# main_board.net
KiCad netlist of a schematic drawn in EAGLE
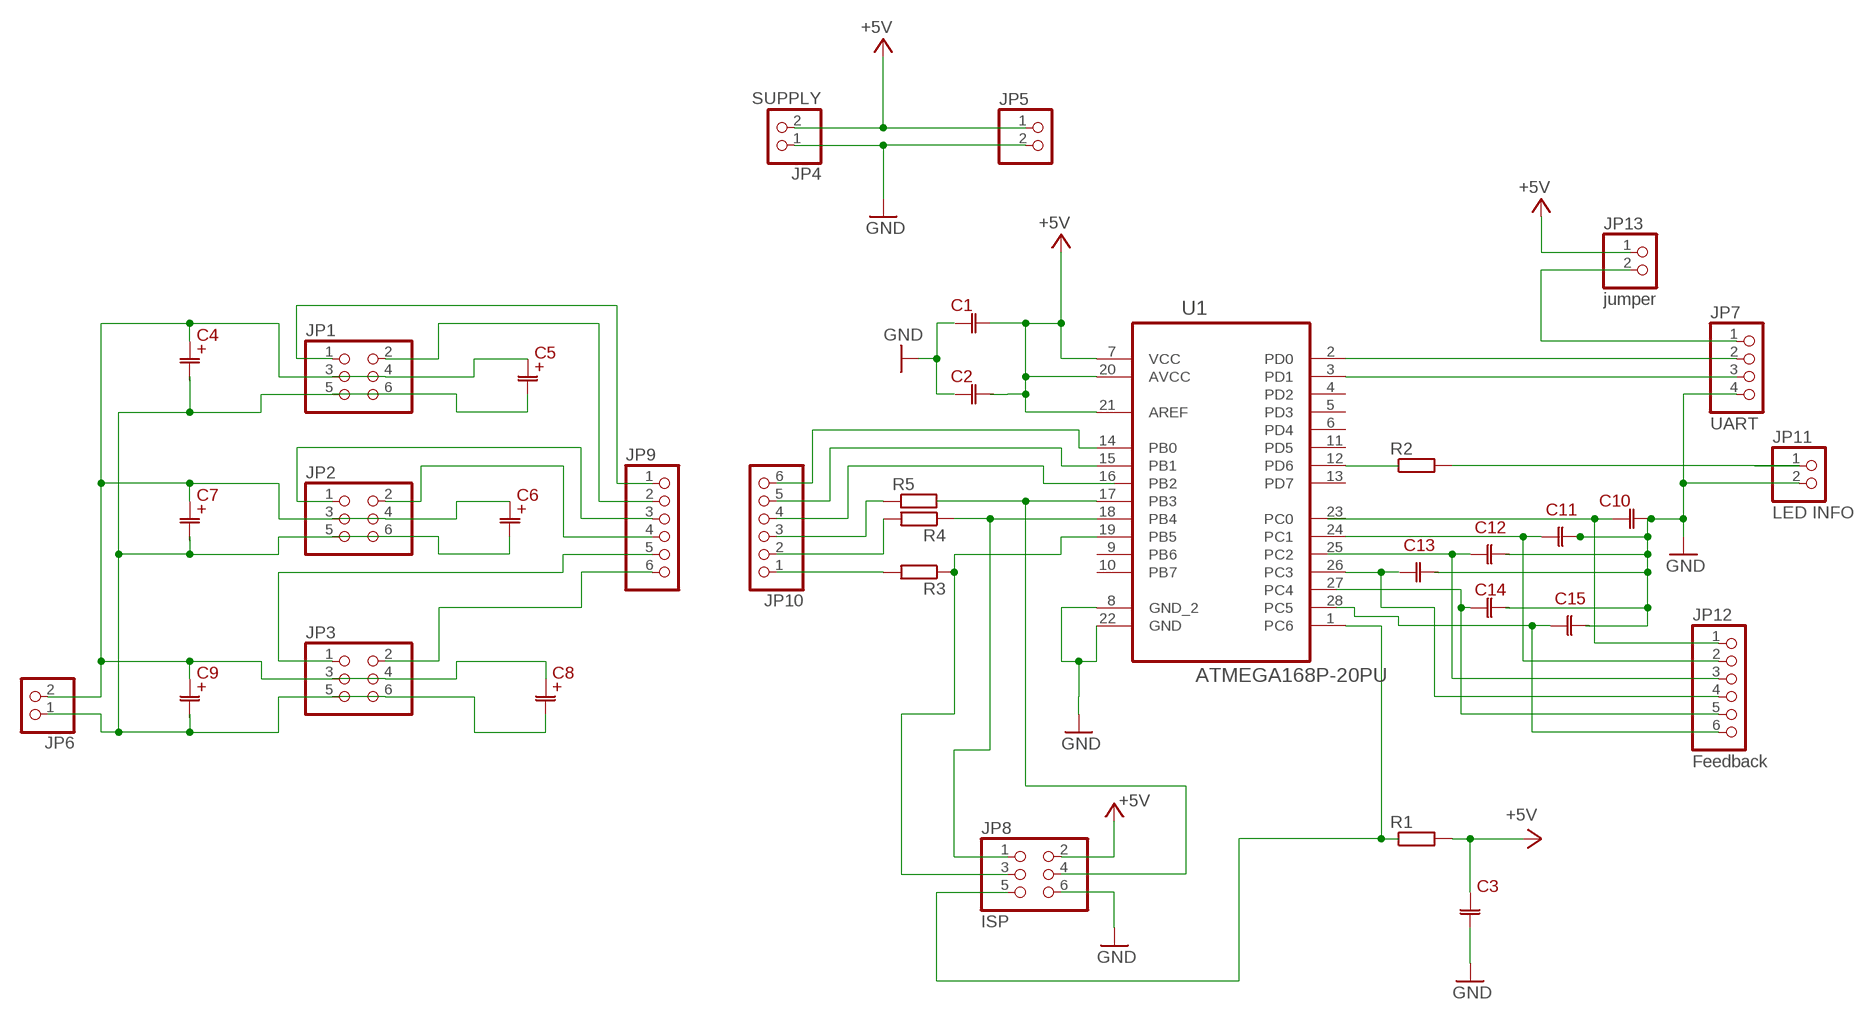
[diagram p0: schematic, sheet 1]

(export (version "E")
  (design (tool "Eeschema 10.0.6"))
  (components
    (comp (ref "C1")
      (value "C-UA")
      (footprint "eagle-import:C2225K")
      (libsource (lib "eagle-import") (part "C-UA"))
    )
    (comp (ref "C2")
      (value "C-UA")
      (footprint "eagle-import:C2225K")
      (libsource (lib "eagle-import") (part "C-UA"))
    )
    (comp (ref "C3")
      (value "C-UA")
      (footprint "eagle-import:C2225K")
      (libsource (lib "eagle-import") (part "C-UA"))
    )
    (comp (ref "C4")
      (value "CPOL-UA")
      (footprint "eagle-import:E3,5-8")
      (libsource (lib "eagle-import") (part "CPOL-UA"))
    )
    (comp (ref "C5")
      (value "CPOL-UA")
      (footprint "eagle-import:E3,5-8")
      (libsource (lib "eagle-import") (part "CPOL-UA"))
    )
    (comp (ref "C6")
      (value "CPOL-UA")
      (footprint "eagle-import:E3,5-8")
      (libsource (lib "eagle-import") (part "CPOL-UA"))
    )
    (comp (ref "C7")
      (value "CPOL-UA")
      (footprint "eagle-import:E3,5-8")
      (libsource (lib "eagle-import") (part "CPOL-UA"))
    )
    (comp (ref "C8")
      (value "CPOL-UA")
      (footprint "eagle-import:E3,5-8")
      (libsource (lib "eagle-import") (part "CPOL-UA"))
    )
    (comp (ref "C9")
      (value "CPOL-UA")
      (footprint "eagle-import:E3,5-8")
      (libsource (lib "eagle-import") (part "CPOL-UA"))
    )
    (comp (ref "C10")
      (value "C-UA")
      (footprint "eagle-import:C2225K")
      (libsource (lib "eagle-import") (part "C-UA"))
    )
    (comp (ref "C11")
      (value "C-UA")
      (footprint "eagle-import:C2225K")
      (libsource (lib "eagle-import") (part "C-UA"))
    )
    (comp (ref "C12")
      (value "C-UA")
      (footprint "eagle-import:C2225K")
      (libsource (lib "eagle-import") (part "C-UA"))
    )
    (comp (ref "C13")
      (value "C-UA")
      (footprint "eagle-import:C2225K")
      (libsource (lib "eagle-import") (part "C-UA"))
    )
    (comp (ref "C14")
      (value "C-UA")
      (footprint "eagle-import:C2225K")
      (libsource (lib "eagle-import") (part "C-UA"))
    )
    (comp (ref "C15")
      (value "C-UA")
      (footprint "eagle-import:C2225K")
      (libsource (lib "eagle-import") (part "C-UA"))
    )
    (comp (ref "JP1")
      (value "PINHD-2X3")
      (footprint "eagle-import:2X03")
      (libsource (lib "eagle-import") (part "PINHD-2X3"))
    )
    (comp (ref "JP2")
      (value "PINHD-2X3")
      (footprint "eagle-import:2X03")
      (libsource (lib "eagle-import") (part "PINHD-2X3"))
    )
    (comp (ref "JP3")
      (value "PINHD-2X3")
      (footprint "eagle-import:2X03")
      (libsource (lib "eagle-import") (part "PINHD-2X3"))
    )
    (comp (ref "JP4")
      (value "SUPPLY")
      (footprint "eagle-import:1X02")
      (libsource (lib "eagle-import") (part "PINHD-1X2"))
    )
    (comp (ref "JP5")
      (value "PINHD-1X2")
      (footprint "eagle-import:1X02")
      (libsource (lib "eagle-import") (part "PINHD-1X2"))
    )
    (comp (ref "JP6")
      (value "PINHD-1X2")
      (footprint "eagle-import:1X02")
      (libsource (lib "eagle-import") (part "PINHD-1X2"))
    )
    (comp (ref "JP7")
      (value "UART")
      (footprint "eagle-import:1X04")
      (libsource (lib "eagle-import") (part "PINHD-1X4"))
    )
    (comp (ref "JP8")
      (value "ISP")
      (footprint "eagle-import:2X03")
      (libsource (lib "eagle-import") (part "PINHD-2X3"))
    )
    (comp (ref "JP9")
      (value "PINHD-1X6")
      (footprint "eagle-import:1X06")
      (libsource (lib "eagle-import") (part "PINHD-1X6"))
    )
    (comp (ref "JP10")
      (value "PINHD-1X6")
      (footprint "eagle-import:1X06")
      (libsource (lib "eagle-import") (part "PINHD-1X6"))
    )
    (comp (ref "JP11")
      (value "LED INFO")
      (footprint "eagle-import:1X02")
      (libsource (lib "eagle-import") (part "PINHD-1X2"))
    )
    (comp (ref "JP12")
      (value "Feedback")
      (footprint "eagle-import:1X06")
      (libsource (lib "eagle-import") (part "PINHD-1X6"))
    )
    (comp (ref "JP13")
      (value "jumper")
      (footprint "eagle-import:1X02")
      (libsource (lib "eagle-import") (part "PINHD-1X2"))
    )
    (comp (ref "R1")
      (value "R-EU_0204/2V")
      (footprint "eagle-import:0204V")
      (libsource (lib "eagle-import") (part "R-EU_0204/2V"))
    )
    (comp (ref "R2")
      (value "R-EU_0204/2V")
      (footprint "eagle-import:0204V")
      (libsource (lib "eagle-import") (part "R-EU_0204/2V"))
    )
    (comp (ref "R3")
      (value "R-EU_0204/2V")
      (footprint "eagle-import:0204V")
      (libsource (lib "eagle-import") (part "R-EU_0204/2V"))
    )
    (comp (ref "R4")
      (value "R-EU_0204/2V")
      (footprint "eagle-import:0204V")
      (libsource (lib "eagle-import") (part "R-EU_0204/2V"))
    )
    (comp (ref "R5")
      (value "R-EU_0204/2V")
      (footprint "eagle-import:0204V")
      (libsource (lib "eagle-import") (part "R-EU_0204/2V"))
    )
    (comp (ref "U1")
      (value "ATMEGA168P-20PU")
      (footprint "eagle-import:DIP254P762X457-28")
      (libsource (lib "eagle-import") (part "ATMEGA168P-20PU"))
    )
  )
  (nets
    (net (code "1") (name "+5V") (class "Default")
      (node (ref "JP13") (pin "1") (pinfunction "1_1") (pintype "passive"))
      (node (ref "JP4") (pin "2") (pinfunction "2_2") (pintype "passive"))
      (node (ref "JP5") (pin "1") (pinfunction "1_1") (pintype "passive"))
      (node (ref "JP8") (pin "2") (pinfunction "2_2") (pintype "passive"))
      (node (ref "R1") (pin "2") (pinfunction "2_2") (pintype "passive"))
      (node (ref "U1") (pin "20") (pinfunction "AVCC_20") (pintype "power_in"))
      (node (ref "U1") (pin "21") (pinfunction "AREF_21") (pintype "input"))
      (node (ref "U1") (pin "7") (pinfunction "VCC_7") (pintype "power_in"))
    )
    (net (code "2") (name "GND") (class "Default")
      (node (ref "C10") (pin "2") (pinfunction "2_2") (pintype "passive"))
      (node (ref "C11") (pin "2") (pinfunction "2_2") (pintype "passive"))
      (node (ref "C12") (pin "2") (pinfunction "2_2") (pintype "passive"))
      (node (ref "C13") (pin "2") (pinfunction "2_2") (pintype "passive"))
      (node (ref "C14") (pin "2") (pinfunction "2_2") (pintype "passive"))
      (node (ref "C15") (pin "2") (pinfunction "2_2") (pintype "passive"))
      (node (ref "C3") (pin "2") (pinfunction "2_2") (pintype "passive"))
      (node (ref "JP11") (pin "2") (pinfunction "2_2") (pintype "passive"))
      (node (ref "JP4") (pin "1") (pinfunction "1_1") (pintype "passive"))
      (node (ref "JP5") (pin "2") (pinfunction "2_2") (pintype "passive"))
      (node (ref "JP7") (pin "4") (pinfunction "4_4") (pintype "passive"))
      (node (ref "JP8") (pin "6") (pinfunction "6_6") (pintype "passive"))
      (node (ref "U1") (pin "22") (pinfunction "GND_22") (pintype "passive"))
      (node (ref "U1") (pin "8") (pinfunction "GND_2_8") (pintype "passive"))
    )
    (net (code "3") (name "Net-(C4-Pad-)") (class "Default")
      (node (ref "C4") (pin "-") (pinfunction "-_-") (pintype "passive"))
      (node (ref "JP1") (pin "5") (pinfunction "5_5") (pintype "passive"))
      (node (ref "JP1") (pin "6") (pinfunction "6_6") (pintype "passive"))
      (node (ref "JP2") (pin "5") (pinfunction "5_5") (pintype "passive"))
      (node (ref "JP2") (pin "6") (pinfunction "6_6") (pintype "passive"))
      (node (ref "JP3") (pin "5") (pinfunction "5_5") (pintype "passive"))
      (node (ref "JP3") (pin "6") (pinfunction "6_6") (pintype "passive"))
      (node (ref "JP6") (pin "1") (pinfunction "1_1") (pintype "passive"))
    )
    (net (code "4") (name "Net-(JP1-Pad1)") (class "Default")
      (node (ref "JP1") (pin "1") (pinfunction "1_1") (pintype "passive"))
      (node (ref "JP9") (pin "1") (pinfunction "1_1") (pintype "passive"))
    )
    (net (code "5") (name "Net-(JP1-Pad2)") (class "Default")
      (node (ref "JP1") (pin "2") (pinfunction "2_2") (pintype "passive"))
      (node (ref "JP9") (pin "2") (pinfunction "2_2") (pintype "passive"))
    )
    (net (code "6") (name "Net-(JP1-Pad3)") (class "Default")
      (node (ref "JP1") (pin "3") (pinfunction "3_3") (pintype "passive"))
      (node (ref "JP1") (pin "4") (pinfunction "4_4") (pintype "passive"))
      (node (ref "JP2") (pin "3") (pinfunction "3_3") (pintype "passive"))
      (node (ref "JP2") (pin "4") (pinfunction "4_4") (pintype "passive"))
      (node (ref "JP3") (pin "3") (pinfunction "3_3") (pintype "passive"))
      (node (ref "JP3") (pin "4") (pinfunction "4_4") (pintype "passive"))
      (node (ref "JP6") (pin "2") (pinfunction "2_2") (pintype "passive"))
    )
    (net (code "7") (name "Net-(JP2-Pad1)") (class "Default")
      (node (ref "JP2") (pin "1") (pinfunction "1_1") (pintype "passive"))
      (node (ref "JP9") (pin "3") (pinfunction "3_3") (pintype "passive"))
    )
    (net (code "8") (name "Net-(JP2-Pad2)") (class "Default")
      (node (ref "JP2") (pin "2") (pinfunction "2_2") (pintype "passive"))
      (node (ref "JP9") (pin "4") (pinfunction "4_4") (pintype "passive"))
    )
    (net (code "9") (name "Net-(JP3-Pad1)") (class "Default")
      (node (ref "JP3") (pin "1") (pinfunction "1_1") (pintype "passive"))
      (node (ref "JP9") (pin "5") (pinfunction "5_5") (pintype "passive"))
    )
    (net (code "10") (name "Net-(JP3-Pad2)") (class "Default")
      (node (ref "JP3") (pin "2") (pinfunction "2_2") (pintype "passive"))
      (node (ref "JP9") (pin "6") (pinfunction "6_6") (pintype "passive"))
    )
    (net (code "11") (name "Net-(JP10-Pad1)") (class "Default")
      (node (ref "JP10") (pin "1") (pinfunction "1_1") (pintype "passive"))
      (node (ref "R3") (pin "2") (pinfunction "2_2") (pintype "passive"))
    )
    (net (code "12") (name "Net-(JP10-Pad2)") (class "Default")
      (node (ref "JP10") (pin "2") (pinfunction "2_2") (pintype "passive"))
      (node (ref "R4") (pin "2") (pinfunction "2_2") (pintype "passive"))
    )
    (net (code "13") (name "Net-(JP10-Pad3)") (class "Default")
      (node (ref "JP10") (pin "3") (pinfunction "3_3") (pintype "passive"))
      (node (ref "R5") (pin "1") (pinfunction "1_1") (pintype "passive"))
    )
    (net (code "14") (name "Net-(JP11-Pad1)") (class "Default")
      (node (ref "JP11") (pin "1") (pinfunction "1_1") (pintype "passive"))
      (node (ref "R2") (pin "2") (pinfunction "2_2") (pintype "passive"))
    )
    (net (code "15") (name "Net-(JP13-Pad2)") (class "Default")
      (node (ref "JP13") (pin "2") (pinfunction "2_2") (pintype "passive"))
      (node (ref "JP7") (pin "1") (pinfunction "1_1") (pintype "passive"))
    )
    (net (code "16") (name "Net-(U1-PB0)") (class "Default")
      (node (ref "JP10") (pin "6") (pinfunction "6_6") (pintype "passive"))
      (node (ref "U1") (pin "14") (pinfunction "PB0_14") (pintype "bidirectional"))
    )
    (net (code "17") (name "Net-(U1-PB1)") (class "Default")
      (node (ref "JP10") (pin "5") (pinfunction "5_5") (pintype "passive"))
      (node (ref "U1") (pin "15") (pinfunction "PB1_15") (pintype "bidirectional"))
    )
    (net (code "18") (name "Net-(U1-PB3)") (class "Default")
      (node (ref "JP8") (pin "4") (pinfunction "4_4") (pintype "passive"))
      (node (ref "U1") (pin "17") (pinfunction "PB3_17") (pintype "bidirectional"))
    )
    (net (code "19") (name "Net-(U1-PB4)") (class "Default")
      (node (ref "JP8") (pin "1") (pinfunction "1_1") (pintype "passive"))
      (node (ref "R4") (pin "1") (pinfunction "1_1") (pintype "passive"))
      (node (ref "U1") (pin "18") (pinfunction "PB4_18") (pintype "bidirectional"))
    )
    (net (code "20") (name "Net-(U1-PB5)") (class "Default")
      (node (ref "JP8") (pin "3") (pinfunction "3_3") (pintype "passive"))
      (node (ref "R3") (pin "1") (pinfunction "1_1") (pintype "passive"))
      (node (ref "U1") (pin "19") (pinfunction "PB5_19") (pintype "bidirectional"))
    )
    (net (code "21") (name "Net-(U1-PC1)") (class "Default")
      (node (ref "JP12") (pin "2") (pinfunction "2_2") (pintype "passive"))
      (node (ref "U1") (pin "24") (pinfunction "PC1_24") (pintype "bidirectional"))
    )
    (net (code "22") (name "Net-(U1-PC3)") (class "Default")
      (node (ref "JP12") (pin "4") (pinfunction "4_4") (pintype "passive"))
      (node (ref "U1") (pin "26") (pinfunction "PC3_26") (pintype "bidirectional"))
    )
    (net (code "23") (name "Net-(U1-PC6)") (class "Default")
      (node (ref "JP8") (pin "5") (pinfunction "5_5") (pintype "passive"))
      (node (ref "R1") (pin "1") (pinfunction "1_1") (pintype "passive"))
      (node (ref "U1") (pin "1") (pinfunction "PC6_1") (pintype "bidirectional"))
    )
    (net (code "24") (name "Net-(U1-PD0)") (class "Default")
      (node (ref "JP7") (pin "2") (pinfunction "2_2") (pintype "passive"))
      (node (ref "U1") (pin "2") (pinfunction "PD0_2") (pintype "bidirectional"))
    )
    (net (code "25") (name "Net-(U1-PD1)") (class "Default")
      (node (ref "JP7") (pin "3") (pinfunction "3_3") (pintype "passive"))
      (node (ref "U1") (pin "3") (pinfunction "PD1_3") (pintype "bidirectional"))
    )
    (net (code "26") (name "Net-(U1-PD6)") (class "Default")
      (node (ref "R2") (pin "1") (pinfunction "1_1") (pintype "passive"))
      (node (ref "U1") (pin "12") (pinfunction "PD6_12") (pintype "bidirectional"))
    )
    (net (code "27") (name "unconnected-(C1-Pad1)") (class "Default")
      (node (ref "C1") (pin "1") (pinfunction "1_1") (pintype "passive"))
    )
    (net (code "28") (name "unconnected-(C1-Pad2)") (class "Default")
      (node (ref "C1") (pin "2") (pinfunction "2_2") (pintype "passive"))
    )
    (net (code "29") (name "unconnected-(C2-Pad1)") (class "Default")
      (node (ref "C2") (pin "1") (pinfunction "1_1") (pintype "passive"))
    )
    (net (code "30") (name "unconnected-(C2-Pad2)") (class "Default")
      (node (ref "C2") (pin "2") (pinfunction "2_2") (pintype "passive"))
    )
    (net (code "31") (name "unconnected-(C3-Pad1)") (class "Default")
      (node (ref "C3") (pin "1") (pinfunction "1_1") (pintype "passive"))
    )
    (net (code "32") (name "unconnected-(C4-Pad+)") (class "Default")
      (node (ref "C4") (pin "+") (pinfunction "+_+") (pintype "passive"))
    )
    (net (code "33") (name "unconnected-(C5-Pad+)") (class "Default")
      (node (ref "C5") (pin "+") (pinfunction "+_+") (pintype "passive"))
    )
    (net (code "34") (name "unconnected-(C5-Pad-)") (class "Default")
      (node (ref "C5") (pin "-") (pinfunction "-_-") (pintype "passive"))
    )
    (net (code "35") (name "unconnected-(C6-Pad+)") (class "Default")
      (node (ref "C6") (pin "+") (pinfunction "+_+") (pintype "passive"))
    )
    (net (code "36") (name "unconnected-(C6-Pad-)") (class "Default")
      (node (ref "C6") (pin "-") (pinfunction "-_-") (pintype "passive"))
    )
    (net (code "37") (name "unconnected-(C7-Pad+)") (class "Default")
      (node (ref "C7") (pin "+") (pinfunction "+_+") (pintype "passive"))
    )
    (net (code "38") (name "unconnected-(C7-Pad-)") (class "Default")
      (node (ref "C7") (pin "-") (pinfunction "-_-") (pintype "passive"))
    )
    (net (code "39") (name "unconnected-(C8-Pad+)") (class "Default")
      (node (ref "C8") (pin "+") (pinfunction "+_+") (pintype "passive"))
    )
    (net (code "40") (name "unconnected-(C8-Pad-)") (class "Default")
      (node (ref "C8") (pin "-") (pinfunction "-_-") (pintype "passive"))
    )
    (net (code "41") (name "unconnected-(C9-Pad+)") (class "Default")
      (node (ref "C9") (pin "+") (pinfunction "+_+") (pintype "passive"))
    )
    (net (code "42") (name "unconnected-(C9-Pad-)") (class "Default")
      (node (ref "C9") (pin "-") (pinfunction "-_-") (pintype "passive"))
    )
    (net (code "43") (name "unconnected-(C10-Pad1)") (class "Default")
      (node (ref "C10") (pin "1") (pinfunction "1_1") (pintype "passive"))
    )
    (net (code "44") (name "unconnected-(C11-Pad1)") (class "Default")
      (node (ref "C11") (pin "1") (pinfunction "1_1") (pintype "passive"))
    )
    (net (code "45") (name "unconnected-(C12-Pad1)") (class "Default")
      (node (ref "C12") (pin "1") (pinfunction "1_1") (pintype "passive"))
    )
    (net (code "46") (name "unconnected-(C13-Pad1)") (class "Default")
      (node (ref "C13") (pin "1") (pinfunction "1_1") (pintype "passive"))
    )
    (net (code "47") (name "unconnected-(C14-Pad1)") (class "Default")
      (node (ref "C14") (pin "1") (pinfunction "1_1") (pintype "passive"))
    )
    (net (code "48") (name "unconnected-(C15-Pad1)") (class "Default")
      (node (ref "C15") (pin "1") (pinfunction "1_1") (pintype "passive"))
    )
    (net (code "49") (name "unconnected-(JP10-Pad4)") (class "Default")
      (node (ref "JP10") (pin "4") (pinfunction "4_4") (pintype "passive"))
    )
    (net (code "50") (name "unconnected-(JP12-Pad1)") (class "Default")
      (node (ref "JP12") (pin "1") (pinfunction "1_1") (pintype "passive"))
    )
    (net (code "51") (name "unconnected-(JP12-Pad3)") (class "Default")
      (node (ref "JP12") (pin "3") (pinfunction "3_3") (pintype "passive"))
    )
    (net (code "52") (name "unconnected-(JP12-Pad5)") (class "Default")
      (node (ref "JP12") (pin "5") (pinfunction "5_5") (pintype "passive"))
    )
    (net (code "53") (name "unconnected-(JP12-Pad6)") (class "Default")
      (node (ref "JP12") (pin "6") (pinfunction "6_6") (pintype "passive"))
    )
    (net (code "54") (name "unconnected-(R5-Pad2)") (class "Default")
      (node (ref "R5") (pin "2") (pinfunction "2_2") (pintype "passive"))
    )
    (net (code "55") (name "unconnected-(U1-PB2-Pad16)") (class "Default")
      (node (ref "U1") (pin "16") (pinfunction "PB2_16") (pintype "bidirectional"))
    )
    (net (code "56") (name "unconnected-(U1-PB6-Pad9)") (class "Default")
      (node (ref "U1") (pin "9") (pinfunction "PB6_9") (pintype "bidirectional"))
    )
    (net (code "57") (name "unconnected-(U1-PB7-Pad10)") (class "Default")
      (node (ref "U1") (pin "10") (pinfunction "PB7_10") (pintype "bidirectional"))
    )
    (net (code "58") (name "unconnected-(U1-PC0-Pad23)") (class "Default")
      (node (ref "U1") (pin "23") (pinfunction "PC0_23") (pintype "bidirectional"))
    )
    (net (code "59") (name "unconnected-(U1-PC2-Pad25)") (class "Default")
      (node (ref "U1") (pin "25") (pinfunction "PC2_25") (pintype "bidirectional"))
    )
    (net (code "60") (name "unconnected-(U1-PC4-Pad27)") (class "Default")
      (node (ref "U1") (pin "27") (pinfunction "PC4_27") (pintype "bidirectional"))
    )
    (net (code "61") (name "unconnected-(U1-PC5-Pad28)") (class "Default")
      (node (ref "U1") (pin "28") (pinfunction "PC5_28") (pintype "bidirectional"))
    )
    (net (code "62") (name "unconnected-(U1-PD2-Pad4)") (class "Default")
      (node (ref "U1") (pin "4") (pinfunction "PD2_4") (pintype "bidirectional"))
    )
    (net (code "63") (name "unconnected-(U1-PD3-Pad5)") (class "Default")
      (node (ref "U1") (pin "5") (pinfunction "PD3_5") (pintype "bidirectional"))
    )
    (net (code "64") (name "unconnected-(U1-PD4-Pad6)") (class "Default")
      (node (ref "U1") (pin "6") (pinfunction "PD4_6") (pintype "bidirectional"))
    )
    (net (code "65") (name "unconnected-(U1-PD5-Pad11)") (class "Default")
      (node (ref "U1") (pin "11") (pinfunction "PD5_11") (pintype "bidirectional"))
    )
    (net (code "66") (name "unconnected-(U1-PD7-Pad13)") (class "Default")
      (node (ref "U1") (pin "13") (pinfunction "PD7_13") (pintype "bidirectional"))
    )
  )
)
